# weather-station.net
KiCad netlist of a schematic drawn in EAGLE
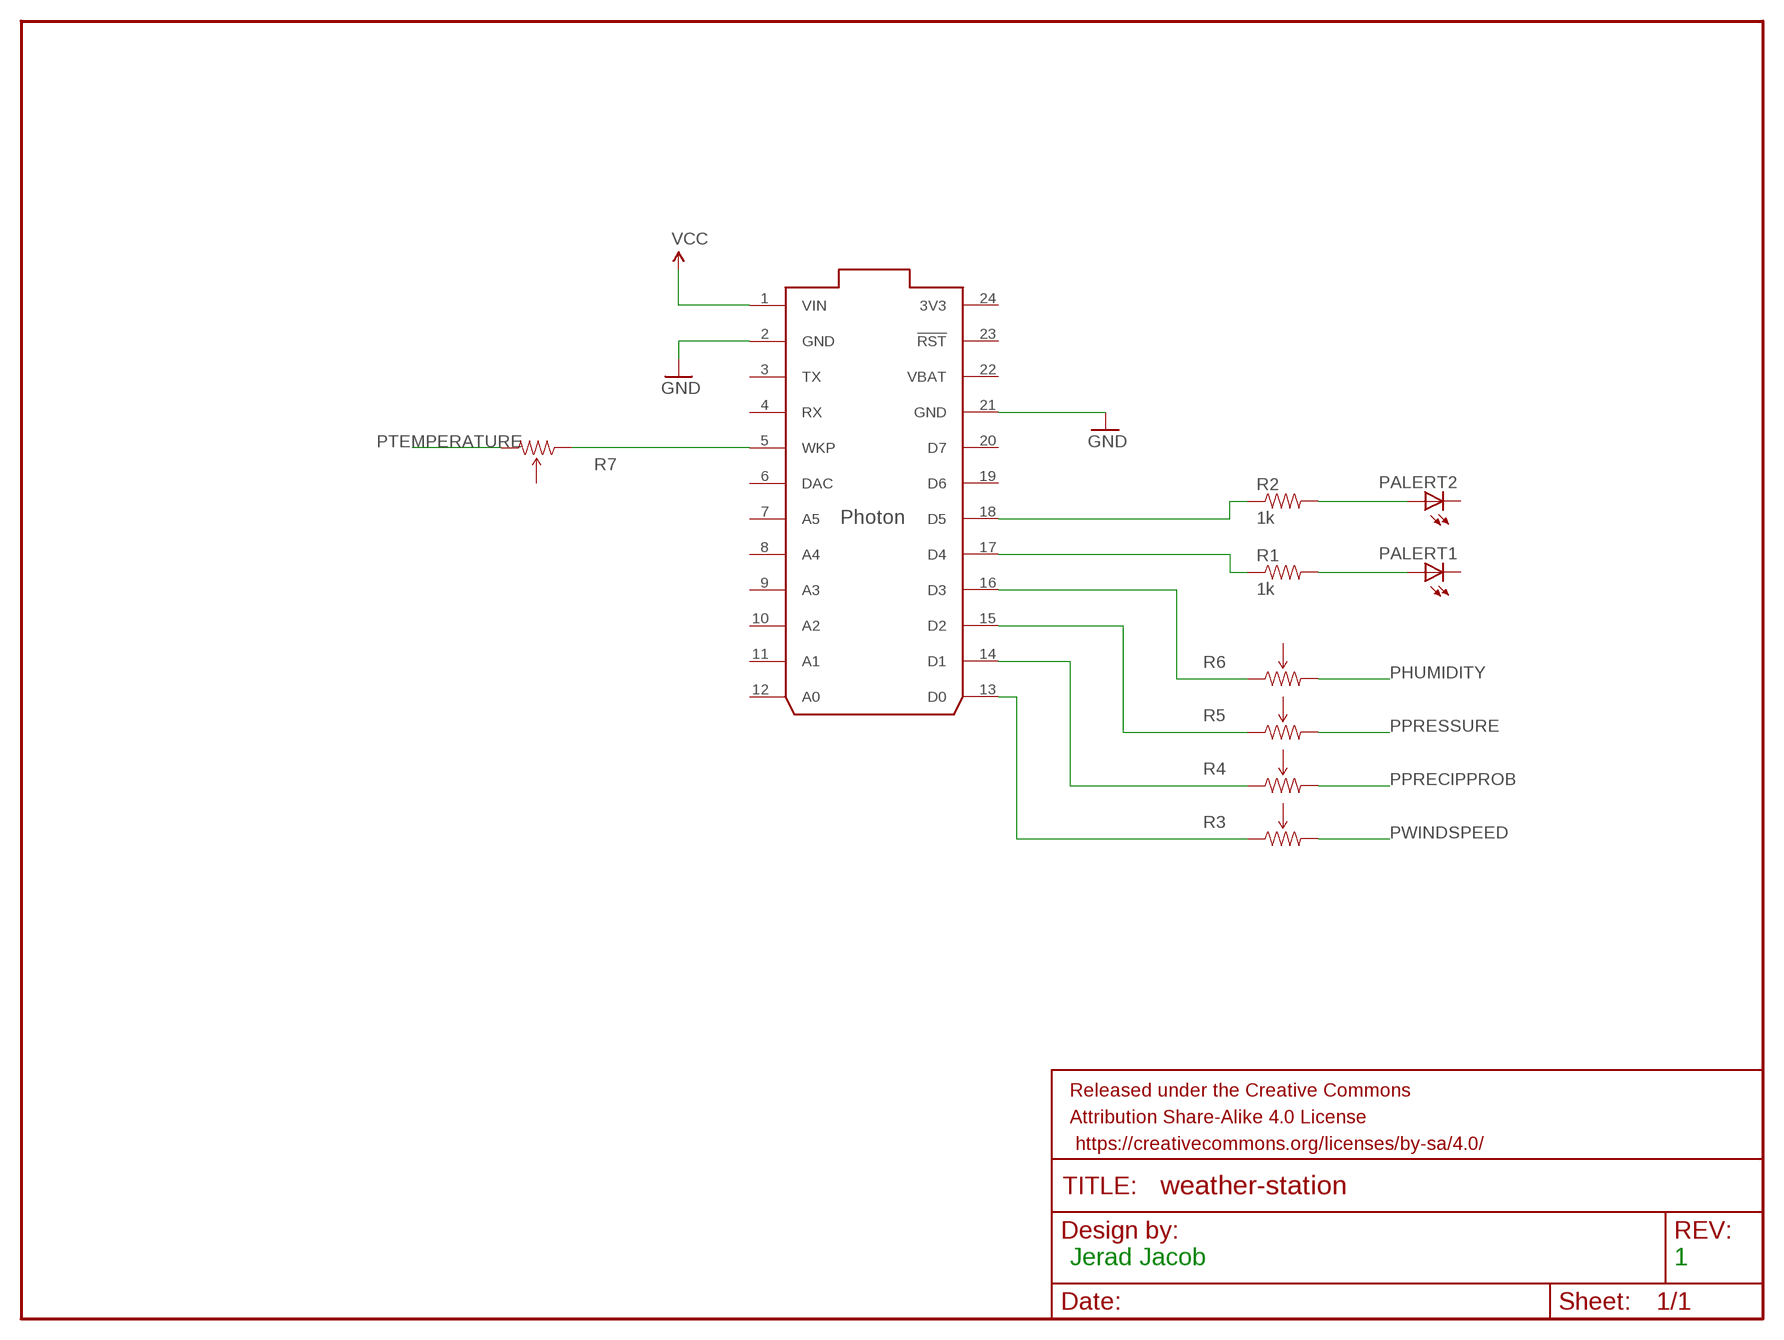
[diagram p0: schematic, sheet 1]

(export (version "E")
  (design (tool "Eeschema 10.0.6"))
  (components
    (comp (ref "FRAME1")
      (value "FRAME-LETTER")
      (footprint "eagle-import:CREATIVE_COMMONS")
      (libsource (lib "eagle-import") (part "FRAME-LETTER"))
    )
    (comp (ref "PALERT1")
      (value "LED5MM")
      (footprint "eagle-import:LED5MM")
      (libsource (lib "eagle-import") (part "LED5MM"))
    )
    (comp (ref "PALERT2")
      (value "LED5MM")
      (footprint "eagle-import:LED5MM")
      (libsource (lib "eagle-import") (part "LED5MM"))
    )
    (comp (ref "R1")
      (value "1k")
      (footprint "eagle-import:AXIAL-0.3")
      (libsource (lib "eagle-import") (part "RESISTORAXIAL-0.3"))
    )
    (comp (ref "R2")
      (value "1k")
      (footprint "eagle-import:AXIAL-0.3")
      (libsource (lib "eagle-import") (part "RESISTORAXIAL-0.3"))
    )
    (comp (ref "R3")
      (value "TRIMPOT")
      (footprint "eagle-import:TRIMPOT-5MM-V2")
      (libsource (lib "eagle-import") (part "TRIMPOT"))
    )
    (comp (ref "R4")
      (value "TRIMPOT")
      (footprint "eagle-import:TRIMPOT-5MM-V2")
      (libsource (lib "eagle-import") (part "TRIMPOT"))
    )
    (comp (ref "R5")
      (value "TRIMPOT")
      (footprint "eagle-import:TRIMPOT-5MM-V2")
      (libsource (lib "eagle-import") (part "TRIMPOT"))
    )
    (comp (ref "R6")
      (value "TRIMPOT")
      (footprint "eagle-import:TRIMPOT-5MM-V2")
      (libsource (lib "eagle-import") (part "TRIMPOT"))
    )
    (comp (ref "R7")
      (value "TRIMPOT")
      (footprint "eagle-import:TRIMPOT-5MM-V2")
      (libsource (lib "eagle-import") (part "TRIMPOT"))
    )
    (comp (ref "U$1")
      (value "PHOTON_WITH_HEADERS")
      (footprint "eagle-import:PHOTON")
      (libsource (lib "eagle-import") (part "PHOTON_WITH_HEADERS"))
    )
  )
  (nets
    (net (code "1") (name "/3V3") (class "Default")
      (node (ref "U$1") (pin "24") (pinfunction "3V3_24") (pintype "power_in"))
    )
    (net (code "2") (name "/PHUMIDITY") (class "Default")
      (node (ref "R6") (pin "C") (pinfunction "CW_C") (pintype "passive"))
    )
    (net (code "3") (name "/PPRECIPPROB") (class "Default")
      (node (ref "R4") (pin "C") (pinfunction "CW_C") (pintype "passive"))
    )
    (net (code "4") (name "/PPRESSURE") (class "Default")
      (node (ref "R5") (pin "C") (pinfunction "CW_C") (pintype "passive"))
    )
    (net (code "5") (name "/PTEMPERATURE") (class "Default")
      (node (ref "R7") (pin "C") (pinfunction "CW_C") (pintype "passive"))
    )
    (net (code "6") (name "/PWINDSPEED") (class "Default")
      (node (ref "R3") (pin "C") (pinfunction "CW_C") (pintype "passive"))
    )
    (net (code "7") (name "/VBAT") (class "Default")
      (node (ref "U$1") (pin "22") (pinfunction "VBAT_22") (pintype "power_in"))
    )
    (net (code "8") (name "GND") (class "Default")
      (node (ref "U$1") (pin "2") (pinfunction "GND_2") (pintype "power_in"))
      (node (ref "U$1") (pin "21") (pinfunction "GND_21") (pintype "power_in"))
    )
    (net (code "9") (name "Net-(R1-1)") (class "Default")
      (node (ref "R1") (pin "P$1") (pinfunction "1_P$1") (pintype "passive"))
      (node (ref "U$1") (pin "17") (pinfunction "D4_17") (pintype "bidirectional"))
    )
    (net (code "10") (name "Net-(R1-2)") (class "Default")
      (node (ref "PALERT1") (pin "A") (pinfunction "A_A") (pintype "passive"))
      (node (ref "R1") (pin "P$2") (pinfunction "2_P$2") (pintype "passive"))
    )
    (net (code "11") (name "Net-(R2-1)") (class "Default")
      (node (ref "R2") (pin "P$1") (pinfunction "1_P$1") (pintype "passive"))
      (node (ref "U$1") (pin "18") (pinfunction "D5_18") (pintype "bidirectional"))
    )
    (net (code "12") (name "Net-(R2-2)") (class "Default")
      (node (ref "PALERT2") (pin "A") (pinfunction "A_A") (pintype "passive"))
      (node (ref "R2") (pin "P$2") (pinfunction "2_P$2") (pintype "passive"))
    )
    (net (code "13") (name "Net-(R3-CCW)") (class "Default")
      (node (ref "R3") (pin "A") (pinfunction "CCW_A") (pintype "passive"))
      (node (ref "U$1") (pin "13") (pinfunction "D0_13") (pintype "bidirectional"))
    )
    (net (code "14") (name "Net-(R4-CCW)") (class "Default")
      (node (ref "R4") (pin "A") (pinfunction "CCW_A") (pintype "passive"))
      (node (ref "U$1") (pin "14") (pinfunction "D1_14") (pintype "bidirectional"))
    )
    (net (code "15") (name "Net-(R5-CCW)") (class "Default")
      (node (ref "R5") (pin "A") (pinfunction "CCW_A") (pintype "passive"))
      (node (ref "U$1") (pin "15") (pinfunction "D2_15") (pintype "bidirectional"))
    )
    (net (code "16") (name "Net-(R6-CCW)") (class "Default")
      (node (ref "R6") (pin "A") (pinfunction "CCW_A") (pintype "passive"))
      (node (ref "U$1") (pin "16") (pinfunction "D3_16") (pintype "bidirectional"))
    )
    (net (code "17") (name "Net-(R7-CCW)") (class "Default")
      (node (ref "R7") (pin "A") (pinfunction "CCW_A") (pintype "passive"))
      (node (ref "U$1") (pin "5") (pinfunction "WKP_5") (pintype "bidirectional"))
    )
    (net (code "18") (name "VCC") (class "Default")
      (node (ref "U$1") (pin "1") (pinfunction "VIN_1") (pintype "power_in"))
    )
    (net (code "19") (name "unconnected-(PALERT1-C-PadK)") (class "Default")
      (node (ref "PALERT1") (pin "K") (pinfunction "C_K") (pintype "passive"))
    )
    (net (code "20") (name "unconnected-(PALERT2-C-PadK)") (class "Default")
      (node (ref "PALERT2") (pin "K") (pinfunction "C_K") (pintype "passive"))
    )
    (net (code "21") (name "unconnected-(R3-WIPER-PadB)") (class "Default")
      (node (ref "R3") (pin "B") (pinfunction "WIPER_B") (pintype "passive"))
    )
    (net (code "22") (name "unconnected-(R4-WIPER-PadB)") (class "Default")
      (node (ref "R4") (pin "B") (pinfunction "WIPER_B") (pintype "passive"))
    )
    (net (code "23") (name "unconnected-(R5-WIPER-PadB)") (class "Default")
      (node (ref "R5") (pin "B") (pinfunction "WIPER_B") (pintype "passive"))
    )
    (net (code "24") (name "unconnected-(R6-WIPER-PadB)") (class "Default")
      (node (ref "R6") (pin "B") (pinfunction "WIPER_B") (pintype "passive"))
    )
    (net (code "25") (name "unconnected-(R7-WIPER-PadB)") (class "Default")
      (node (ref "R7") (pin "B") (pinfunction "WIPER_B") (pintype "passive"))
    )
    (net (code "26") (name "unconnected-(U$1-A0-Pad12)") (class "Default")
      (node (ref "U$1") (pin "12") (pinfunction "A0_12") (pintype "bidirectional"))
    )
    (net (code "27") (name "unconnected-(U$1-A1-Pad11)") (class "Default")
      (node (ref "U$1") (pin "11") (pinfunction "A1_11") (pintype "bidirectional"))
    )
    (net (code "28") (name "unconnected-(U$1-A2-Pad10)") (class "Default")
      (node (ref "U$1") (pin "10") (pinfunction "A2_10") (pintype "bidirectional"))
    )
    (net (code "29") (name "unconnected-(U$1-A3-Pad9)") (class "Default")
      (node (ref "U$1") (pin "9") (pinfunction "A3_9") (pintype "bidirectional"))
    )
    (net (code "30") (name "unconnected-(U$1-A4-Pad8)") (class "Default")
      (node (ref "U$1") (pin "8") (pinfunction "A4_8") (pintype "bidirectional"))
    )
    (net (code "31") (name "unconnected-(U$1-A5-Pad7)") (class "Default")
      (node (ref "U$1") (pin "7") (pinfunction "A5_7") (pintype "bidirectional"))
    )
    (net (code "32") (name "unconnected-(U$1-D6-Pad19)") (class "Default")
      (node (ref "U$1") (pin "19") (pinfunction "D6_19") (pintype "bidirectional"))
    )
    (net (code "33") (name "unconnected-(U$1-D7-Pad20)") (class "Default")
      (node (ref "U$1") (pin "20") (pinfunction "D7_20") (pintype "bidirectional"))
    )
    (net (code "34") (name "unconnected-(U$1-DAC-Pad6)") (class "Default")
      (node (ref "U$1") (pin "6") (pinfunction "DAC_6") (pintype "bidirectional"))
    )
    (net (code "35") (name "unconnected-(U$1-RX-Pad4)") (class "Default")
      (node (ref "U$1") (pin "4") (pinfunction "RX_4") (pintype "bidirectional"))
    )
    (net (code "36") (name "unconnected-(U$1-TX-Pad3)") (class "Default")
      (node (ref "U$1") (pin "3") (pinfunction "TX_3") (pintype "bidirectional"))
    )
    (net (code "37") (name "unconnected-(U$1-~{RST}-Pad23)") (class "Default")
      (node (ref "U$1") (pin "23") (pinfunction "~{RST}_23") (pintype "bidirectional"))
    )
  )
)
